# LED_FADER.net
KiCad netlist of a schematic drawn in Altium Designer
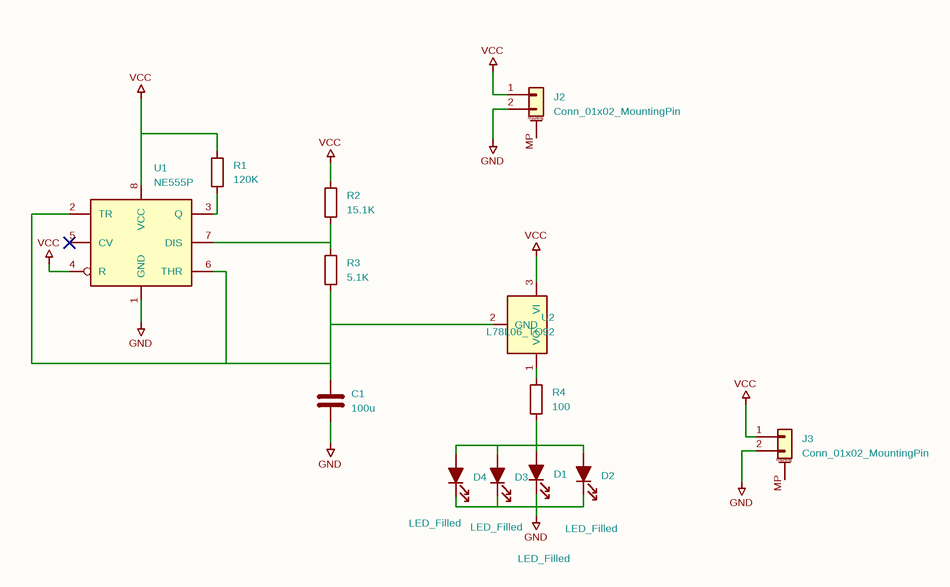
[diagram p0: LED_FADER.SchDoc]

(export (version "E")
  (design (tool "Eeschema 10.0.6"))
  (components
    (comp (ref "C1")
      (value "100u")
      (description "Unpolarized capacitor")
      (libsource (lib "Device") (part "C"))
    )
    (comp (ref "D1")
      (value "LED_Filled")
      (description "Light emitting diode, filled shape")
      (libsource (lib "Device") (part "LED_Filled"))
    )
    (comp (ref "D2")
      (value "LED_Filled")
      (description "Light emitting diode, filled shape")
      (libsource (lib "Device") (part "LED_Filled"))
    )
    (comp (ref "D3")
      (value "LED_Filled")
      (description "Light emitting diode, filled shape")
      (libsource (lib "Device") (part "LED_Filled"))
    )
    (comp (ref "D4")
      (value "LED_Filled")
      (description "Light emitting diode, filled shape")
      (libsource (lib "Device") (part "LED_Filled"))
    )
    (comp (ref "J2")
      (value "Conn_01x02_MountingPin")
      (libsource (lib "Connector_Generic_MountingPin") (part "Conn_01x02_MountingPin"))
    )
    (comp (ref "J3")
      (value "Conn_01x02_MountingPin")
      (libsource (lib "Connector_Generic_MountingPin") (part "Conn_01x02_MountingPin"))
    )
    (comp (ref "R1") (value "120K") (description "Resistor") (libsource (lib "Device") (part "R")))
    (comp (ref "R2") (value "15.1K") (description "Resistor") (libsource (lib "Device") (part "R")))
    (comp (ref "R3") (value "5.1K") (description "Resistor") (libsource (lib "Device") (part "R")))
    (comp (ref "R4") (value "100") (description "Resistor") (libsource (lib "Device") (part "R")))
    (comp (ref "U1")
      (value "NE555P")
      (description "Precision Timers, 555 compatible,  PDIP-8")
      (libsource (lib "Timer") (part "NE555P"))
    )
    (comp (ref "U2")
      (value "L78L06_TO92")
      (description "Positive 100mA 30V Linear Regulator, Fixed Output 6V, TO-92")
      (libsource (lib "Regulator_Linear") (part "L78L06_TO92"))
    )
  )
  (nets
    (net (code "1") (name "GND") (class "Default")
      (node (ref "C1") (pin "2") (pinfunction "2_2") (pintype "passive"))
      (node (ref "D1") (pin "1") (pinfunction "K_1") (pintype "passive"))
      (node (ref "D2") (pin "1") (pinfunction "K_1") (pintype "passive"))
      (node (ref "D3") (pin "1") (pinfunction "K_1") (pintype "passive"))
      (node (ref "D4") (pin "1") (pinfunction "K_1") (pintype "passive"))
      (node (ref "J2") (pin "2") (pinfunction "Pin_2_2") (pintype "passive"))
      (node (ref "J3") (pin "2") (pinfunction "Pin_2_2") (pintype "passive"))
      (node (ref "U1") (pin "1") (pinfunction "GND_1") (pintype "passive"))
    )
    (net (code "2") (name "Net-(D1-A)") (class "Default")
      (node (ref "D1") (pin "2") (pinfunction "A_2") (pintype "passive"))
      (node (ref "D2") (pin "2") (pinfunction "A_2") (pintype "passive"))
      (node (ref "D3") (pin "2") (pinfunction "A_2") (pintype "passive"))
      (node (ref "D4") (pin "2") (pinfunction "A_2") (pintype "passive"))
      (node (ref "R4") (pin "2") (pinfunction "2_2") (pintype "passive"))
    )
    (net (code "3") (name "Net-(U1-DIS)") (class "Default")
      (node (ref "R2") (pin "2") (pinfunction "2_2") (pintype "passive"))
      (node (ref "R3") (pin "1") (pinfunction "1_1") (pintype "passive"))
      (node (ref "U1") (pin "7") (pinfunction "DIS_7") (pintype "passive"))
    )
    (net (code "4") (name "Net-(U1-Q)") (class "Default")
      (node (ref "R1") (pin "2") (pinfunction "2_2") (pintype "passive"))
      (node (ref "U1") (pin "3") (pinfunction "Q_3") (pintype "passive"))
    )
    (net (code "5") (name "Net-(U1-THR)") (class "Default")
      (node (ref "C1") (pin "1") (pinfunction "1_1") (pintype "passive"))
      (node (ref "R3") (pin "2") (pinfunction "2_2") (pintype "passive"))
      (node (ref "U1") (pin "2") (pinfunction "TR_2") (pintype "passive"))
      (node (ref "U1") (pin "6") (pinfunction "THR_6") (pintype "passive"))
      (node (ref "U2") (pin "2") (pinfunction "GND_2") (pintype "passive"))
    )
    (net (code "6") (name "Net-(U2-VO)") (class "Default")
      (node (ref "R4") (pin "1") (pinfunction "1_1") (pintype "passive"))
      (node (ref "U2") (pin "1") (pinfunction "VO_1") (pintype "passive"))
    )
    (net (code "7") (name "VCC") (class "Default")
      (node (ref "J2") (pin "1") (pinfunction "Pin_1_1") (pintype "passive"))
      (node (ref "J3") (pin "1") (pinfunction "Pin_1_1") (pintype "passive"))
      (node (ref "R1") (pin "1") (pinfunction "1_1") (pintype "passive"))
      (node (ref "R2") (pin "1") (pinfunction "1_1") (pintype "passive"))
      (node (ref "U1") (pin "4") (pinfunction "R_4") (pintype "passive"))
      (node (ref "U1") (pin "8") (pinfunction "VCC_8") (pintype "passive"))
      (node (ref "U2") (pin "3") (pinfunction "VI_3") (pintype "passive"))
    )
    (net (code "8") (name "unconnected-(J2-MountPin-PadMP)") (class "Default")
      (node (ref "J2") (pin "MP") (pinfunction "MountPin_MP") (pintype "passive"))
    )
    (net (code "9") (name "unconnected-(J3-MountPin-PadMP)") (class "Default")
      (node (ref "J3") (pin "MP") (pinfunction "MountPin_MP") (pintype "passive"))
    )
    (net (code "10") (name "unconnected-(U1-CV-Pad5)") (class "Default")
      (node (ref "U1") (pin "5") (pinfunction "CV_5") (pintype "passive+no_connect"))
    )
  )
)
